# FIDO2AUTH_003.net
KiCad netlist of a schematic drawn in EAGLE
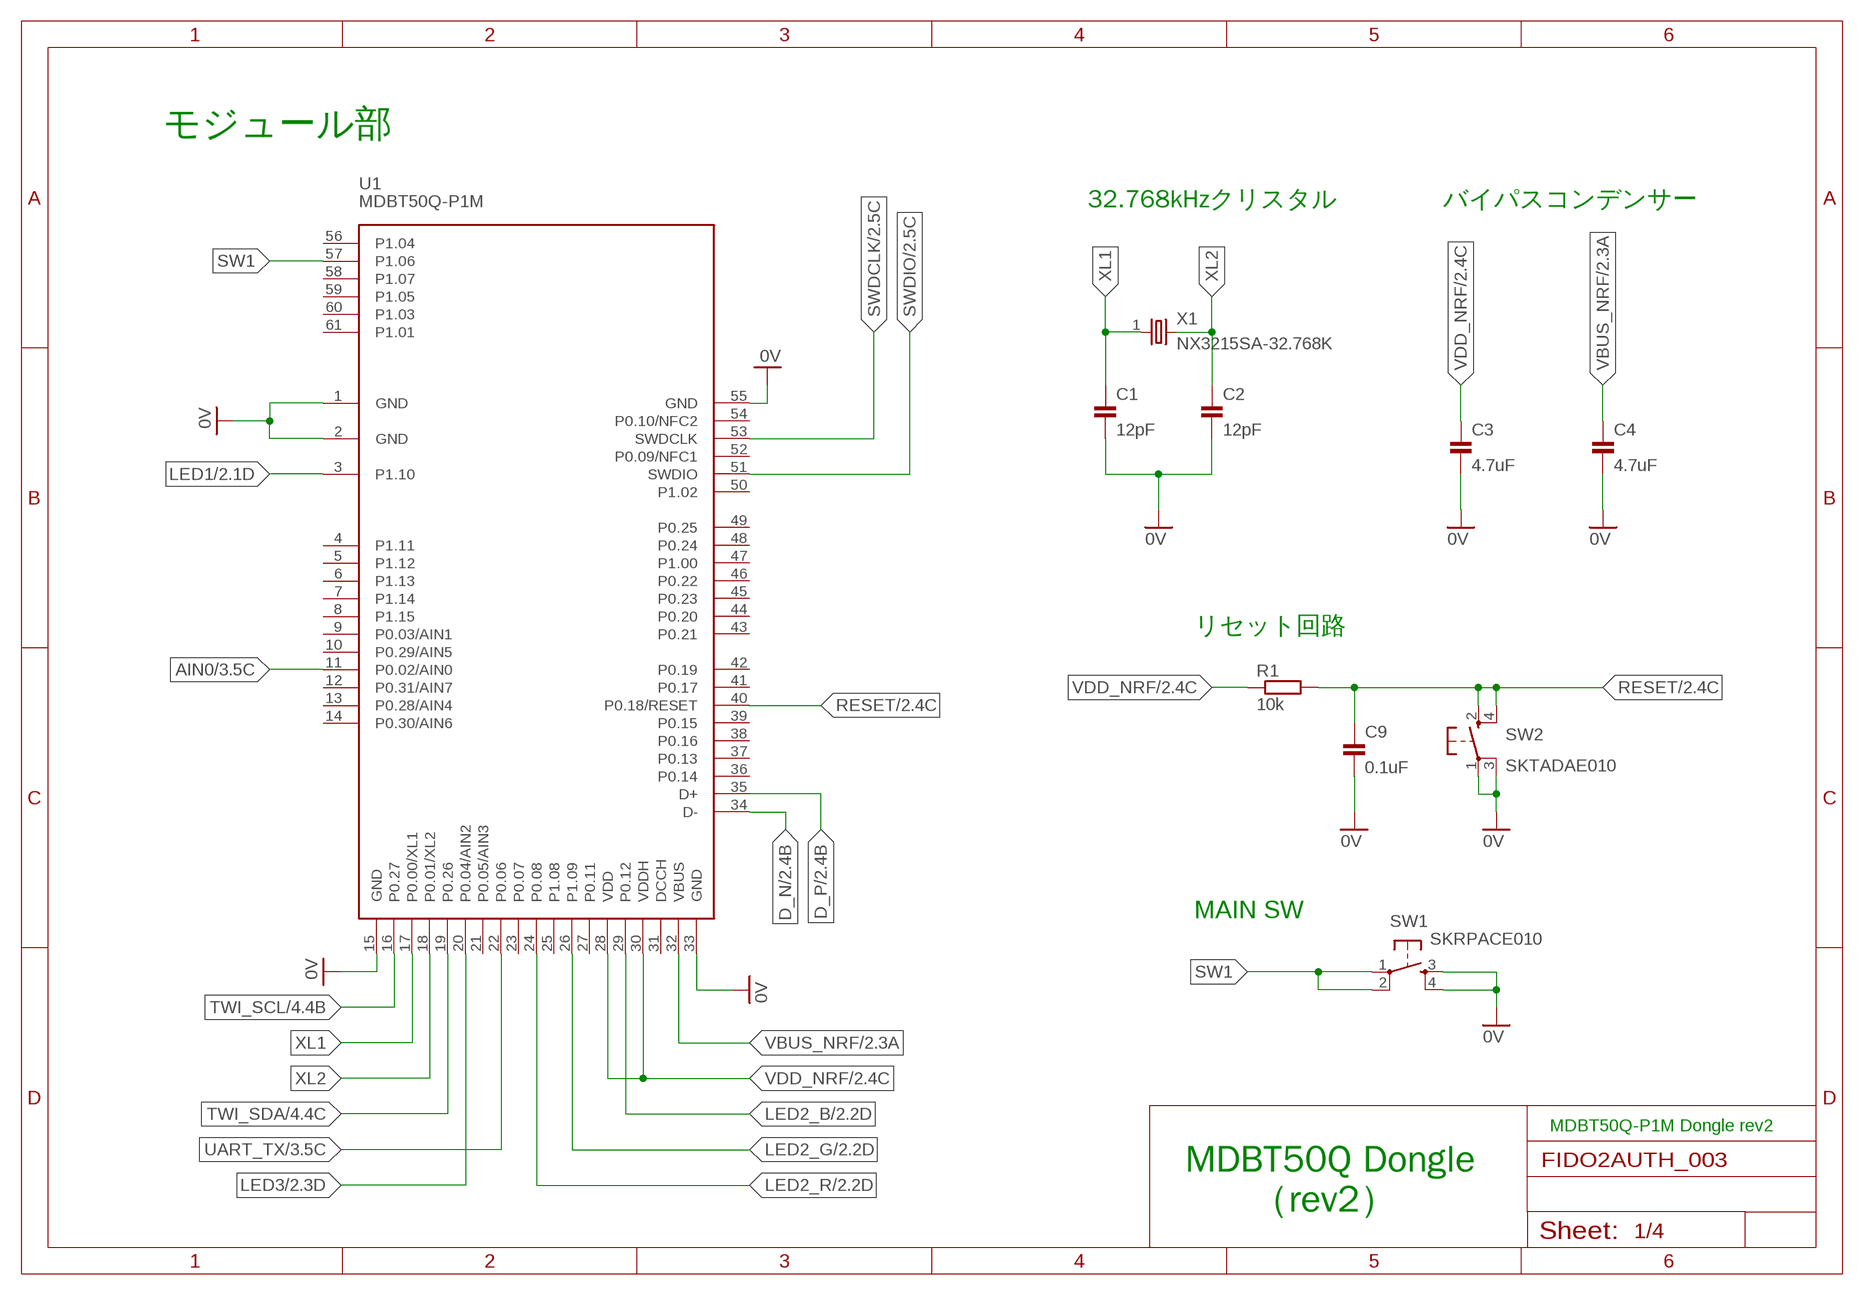
[diagram p0: schematic, sheet 1]
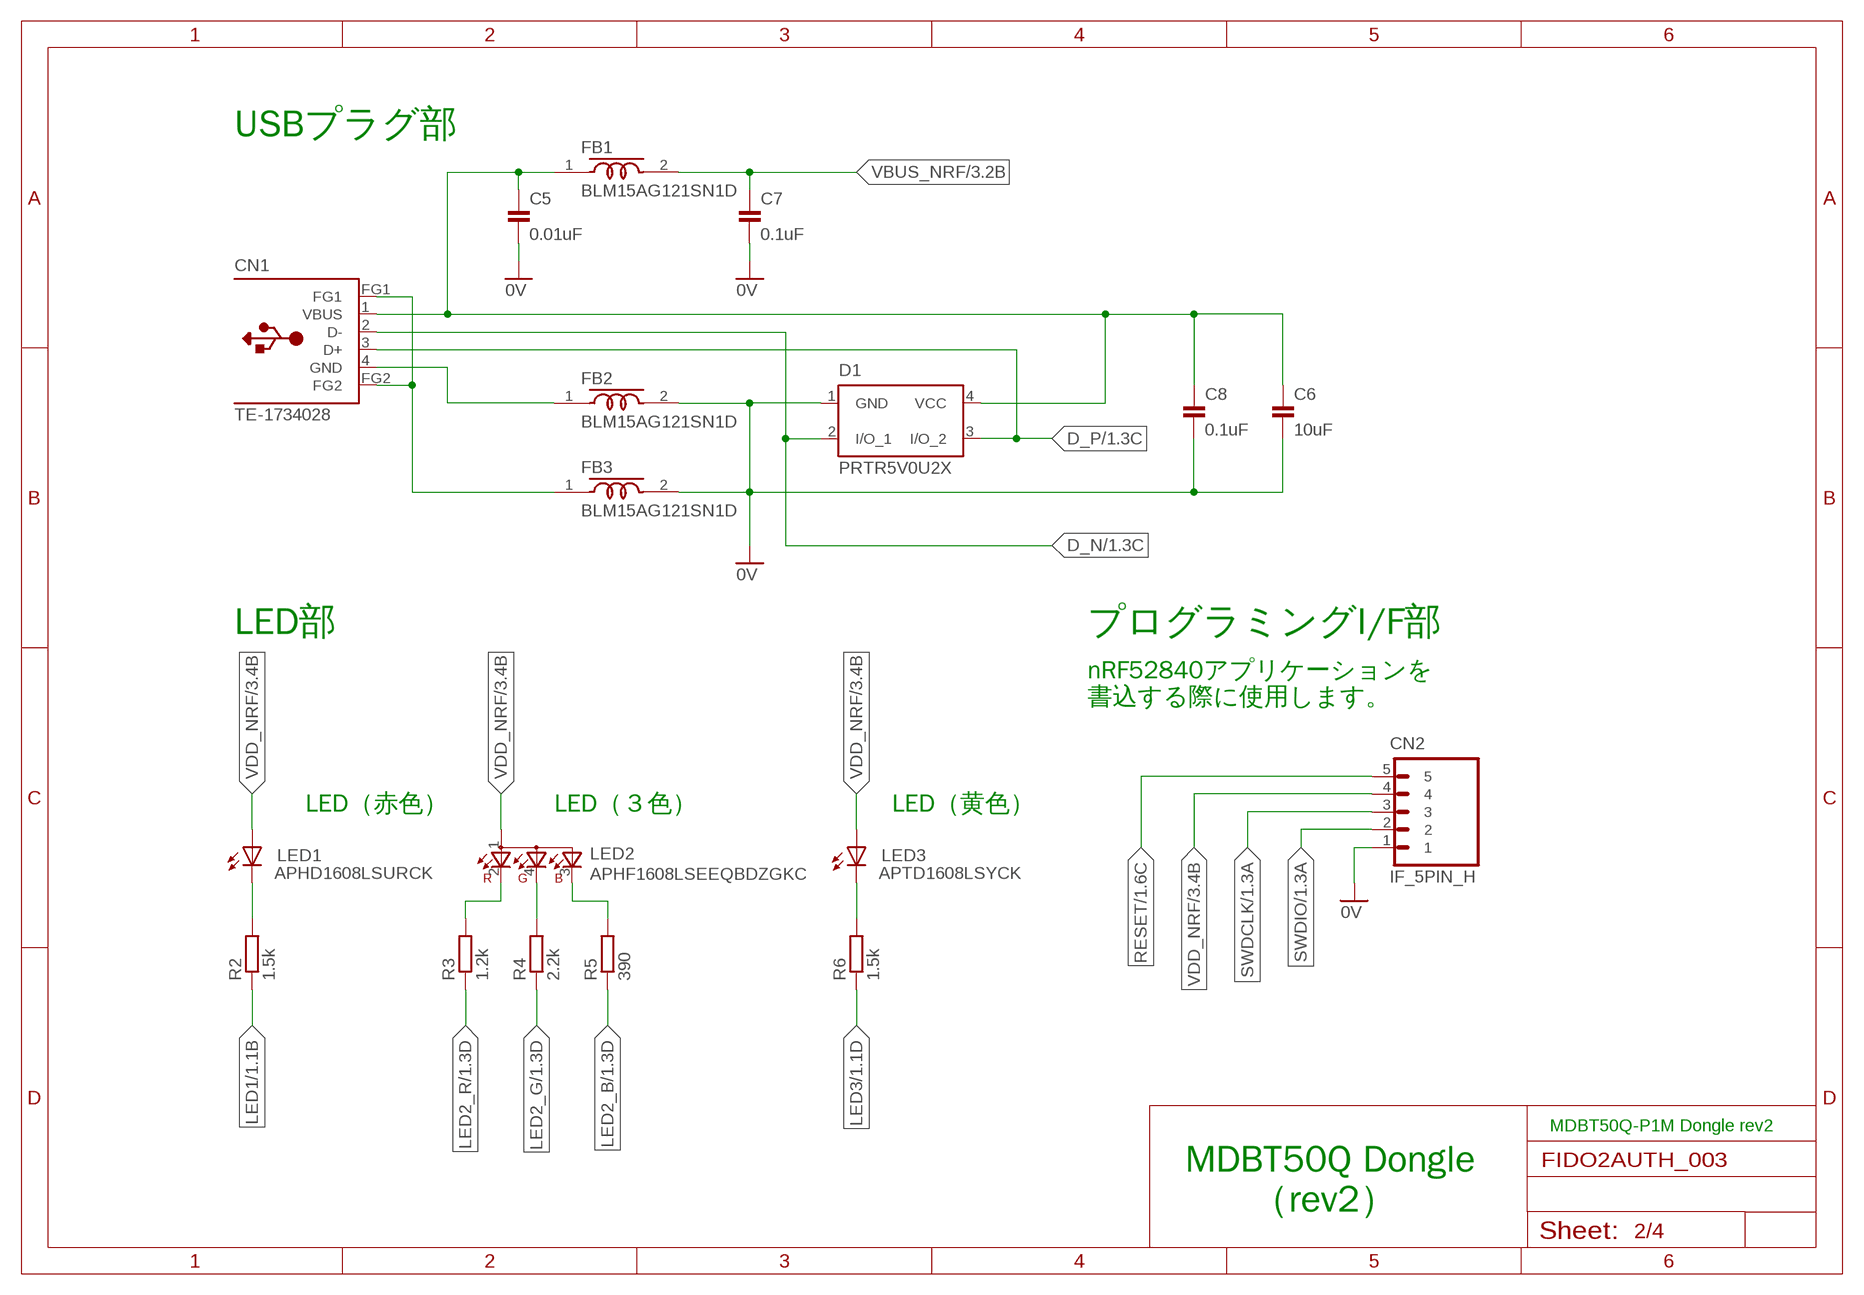
[diagram p1: schematic, sheet 2]
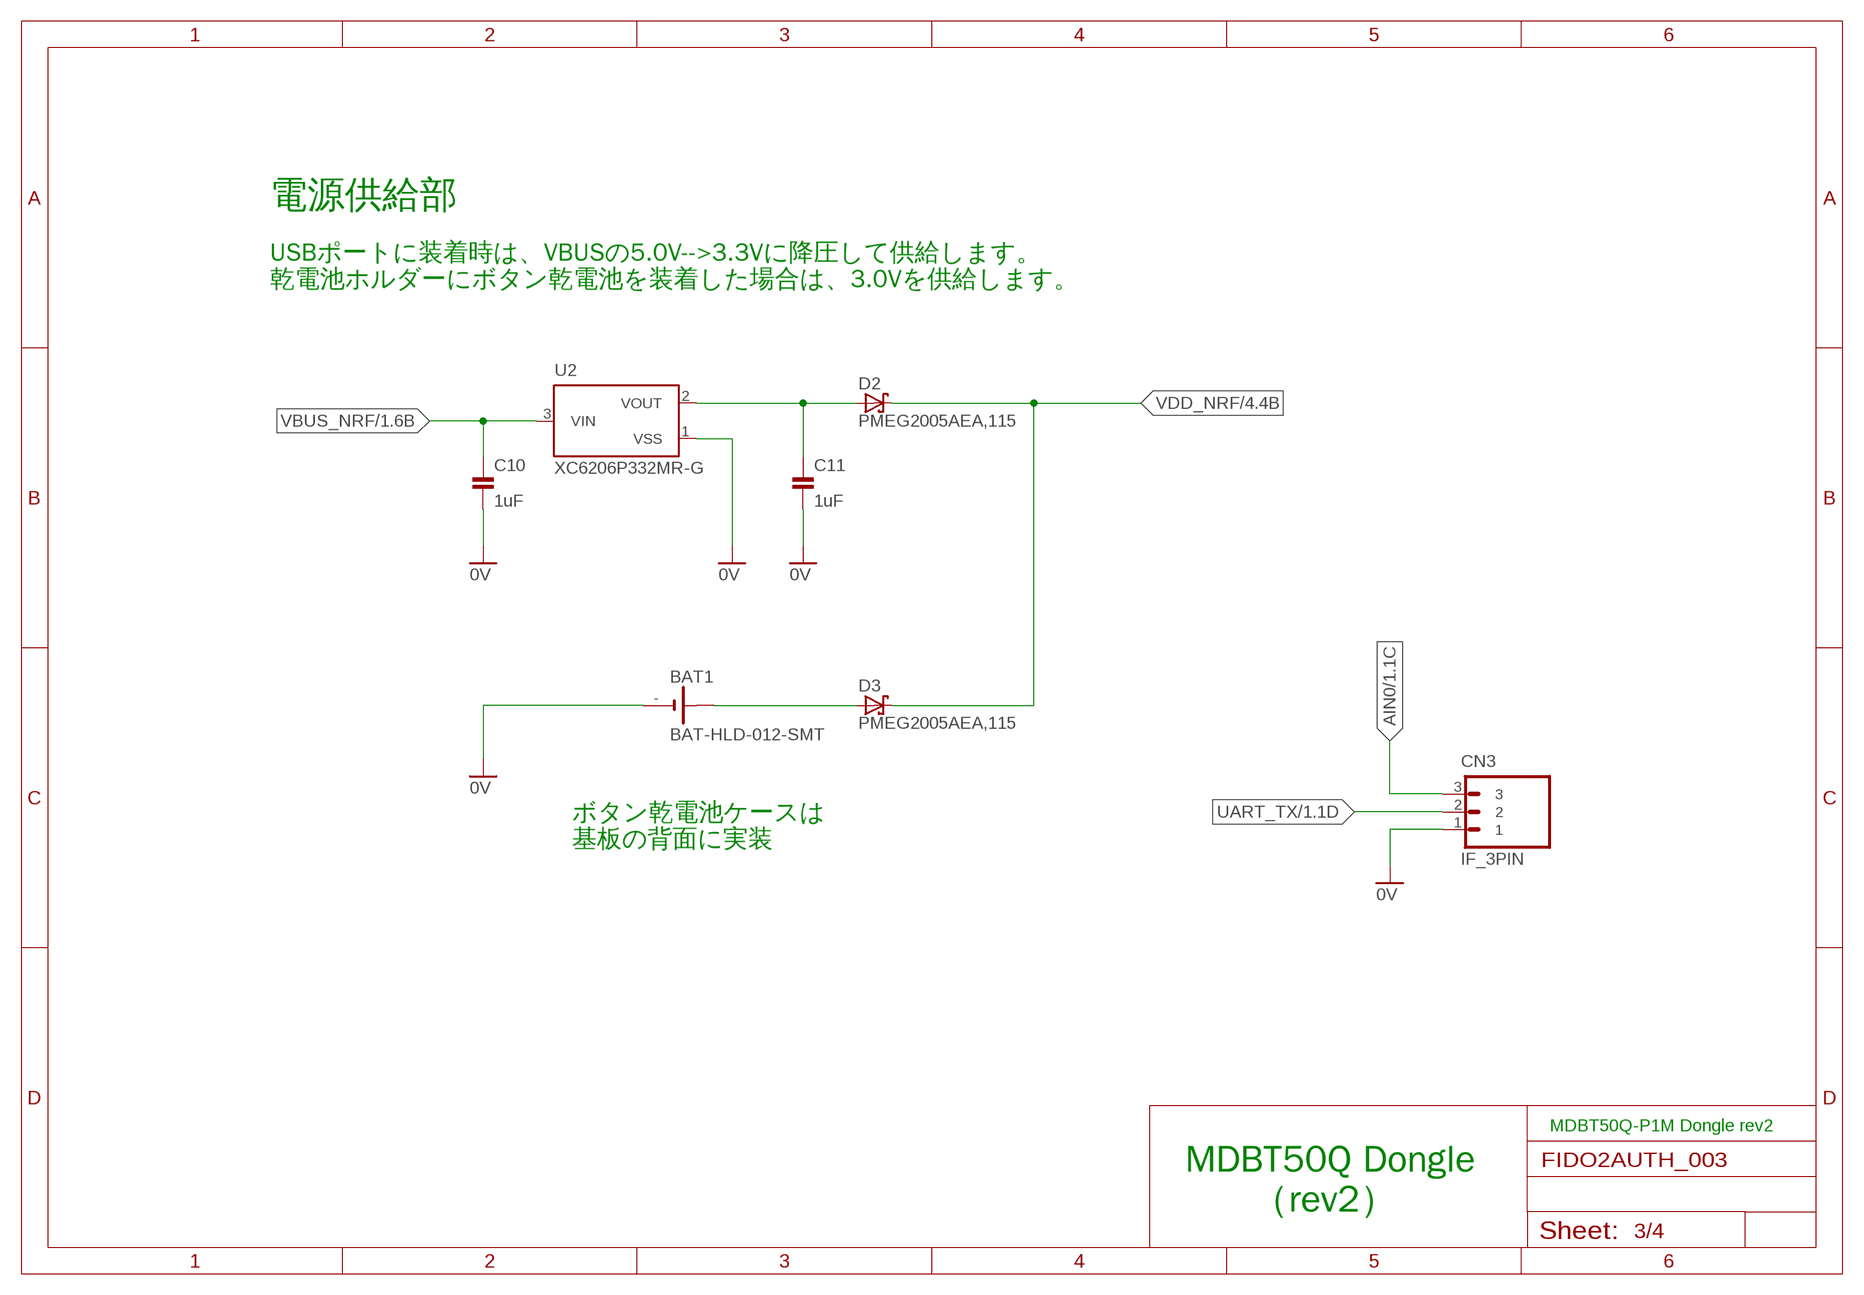
[diagram p2: schematic, sheet 3]
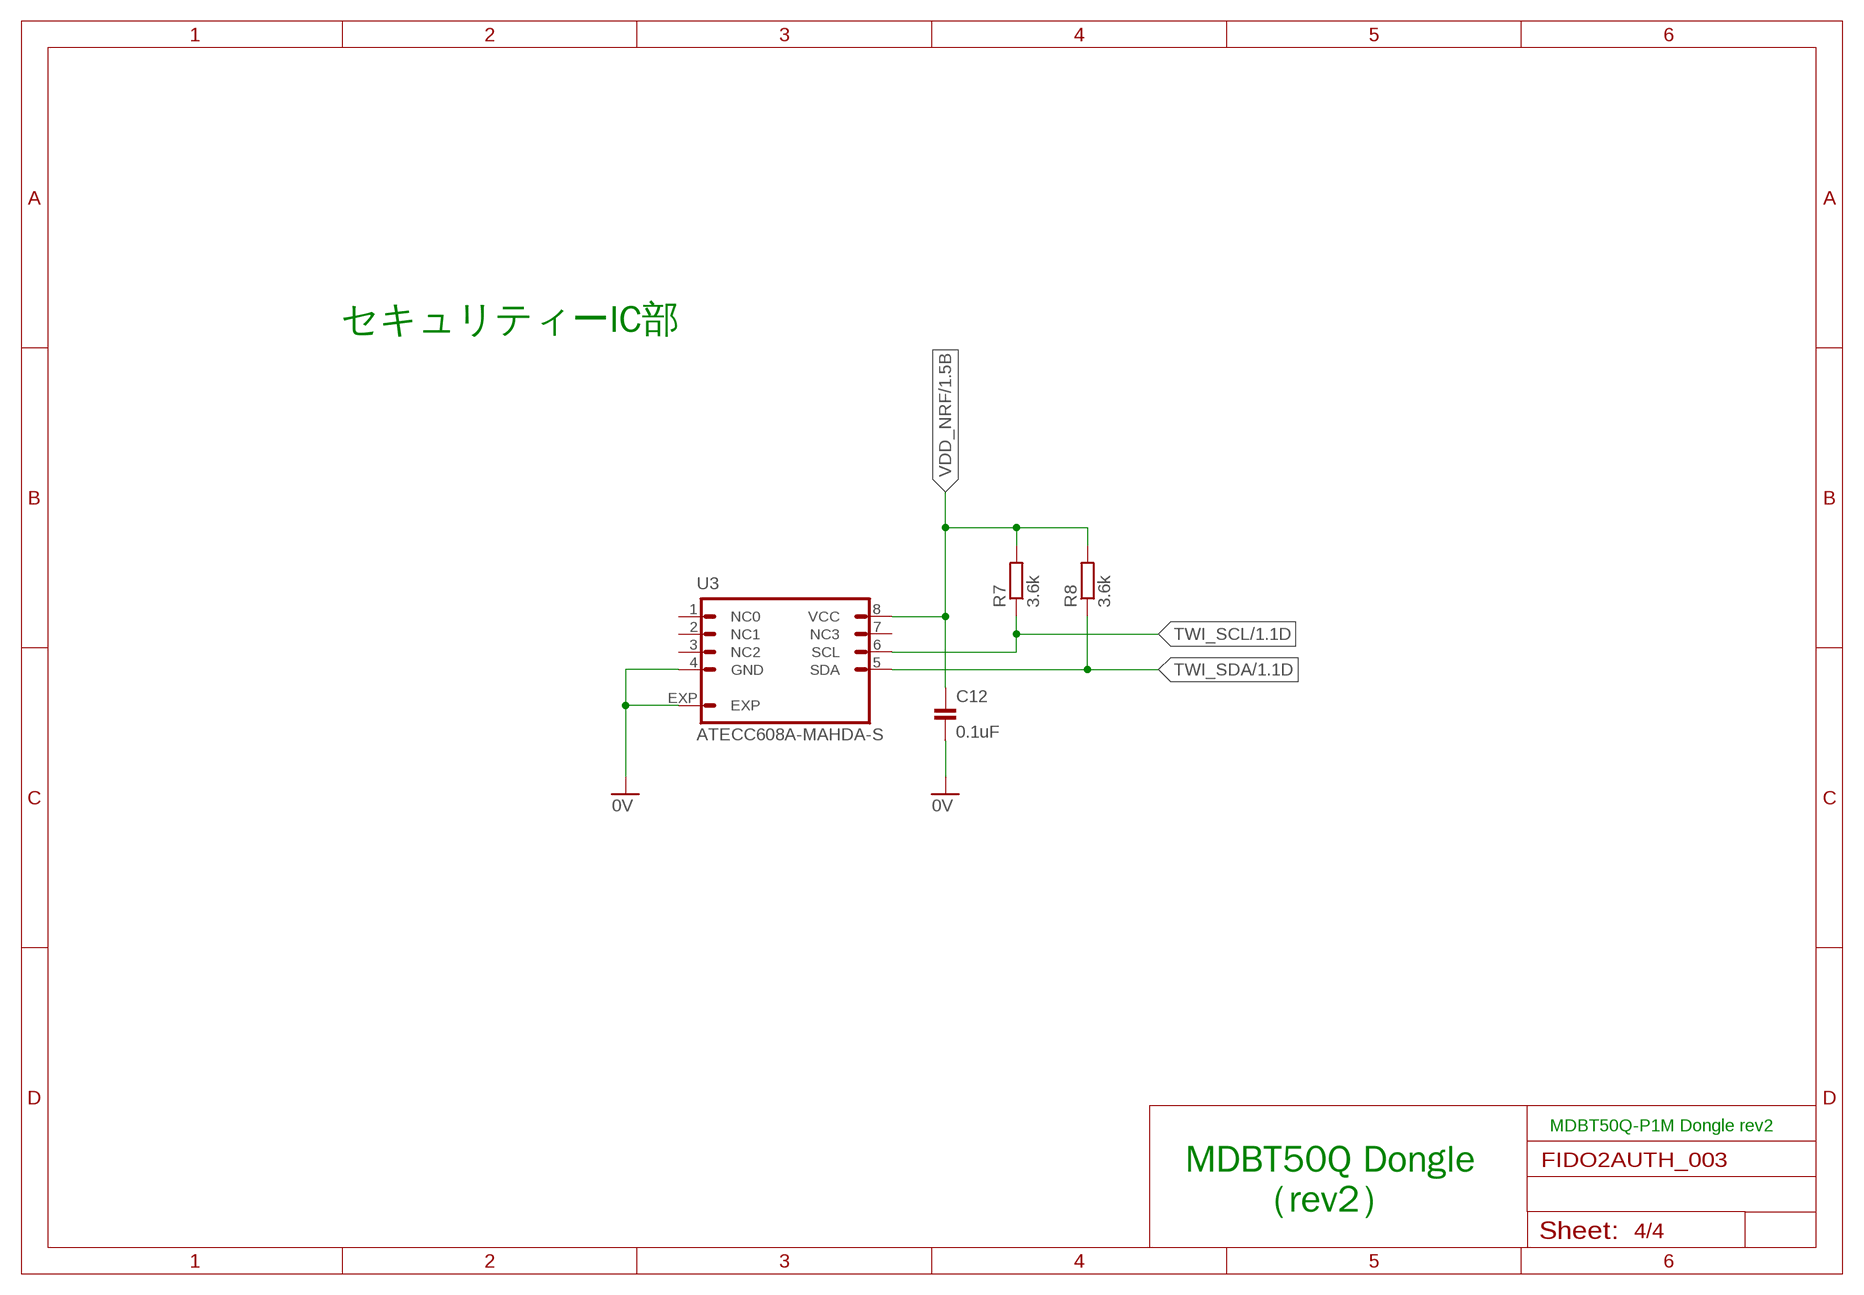
[diagram p3: schematic, sheet 4]

(export (version "E")
  (design (tool "Eeschema 10.0.6"))
  (components
    (comp (ref "C12")
      (value "0.1uF")
      (footprint "eagle-import:C0402K")
      (libsource (lib "eagle-import") (part "CAP_0402"))
    )
    (comp (ref "R7")
      (value "3.6k")
      (footprint "eagle-import:R0402")
      (libsource (lib "eagle-import") (part "RESISTOR_0402"))
    )
    (comp (ref "R8")
      (value "3.6k")
      (footprint "eagle-import:R0402")
      (libsource (lib "eagle-import") (part "RESISTOR_0402"))
    )
    (comp (ref "U3")
      (value "ATECC608A-MAHDA-S")
      (footprint "eagle-import:DFN-2X3")
      (libsource (lib "eagle-import") (part "ATECC608A-MAHDA-S"))
    )
    (comp (ref "C5")
      (value "0.01uF")
      (footprint "eagle-import:C0603K")
      (libsource (lib "eagle-import") (part "CAP_0603"))
    )
    (comp (ref "C6")
      (value "10uF")
      (footprint "eagle-import:C0603K")
      (libsource (lib "eagle-import") (part "CAP_0603"))
    )
    (comp (ref "C7")
      (value "0.1uF")
      (footprint "eagle-import:C0603K")
      (libsource (lib "eagle-import") (part "CAP_0603"))
    )
    (comp (ref "C8")
      (value "0.1uF")
      (footprint "eagle-import:C0603K")
      (libsource (lib "eagle-import") (part "CAP_0603"))
    )
    (comp (ref "CN1")
      (value "TE-1734028")
      (footprint "eagle-import:TE-1734028")
      (libsource (lib "eagle-import") (part "TE-1734028"))
    )
    (comp (ref "CN2")
      (value "IF_5PIN_H")
      (footprint "eagle-import:HEADER_5PIN")
      (libsource (lib "eagle-import") (part "IF_5PIN_H"))
    )
    (comp (ref "D1")
      (value "PRTR5V0U2X")
      (footprint "eagle-import:SOT143B")
      (libsource (lib "eagle-import") (part "PRTR5V0U2X"))
    )
    (comp (ref "FB1")
      (value "BLM15AG121SN1D")
      (footprint "eagle-import:C0402K@1")
      (libsource (lib "eagle-import") (part "BLM15AG121SN1D"))
    )
    (comp (ref "FB2")
      (value "BLM15AG121SN1D")
      (footprint "eagle-import:C0402K@1")
      (libsource (lib "eagle-import") (part "BLM15AG121SN1D"))
    )
    (comp (ref "FB3")
      (value "BLM15AG121SN1D")
      (footprint "eagle-import:C0402K@1")
      (libsource (lib "eagle-import") (part "BLM15AG121SN1D"))
    )
    (comp (ref "LED1")
      (value "APHD1608LSURCK")
      (footprint "eagle-import:CHIPLED_0603")
      (libsource (lib "eagle-import") (part "APHD1608LSURCK"))
    )
    (comp (ref "LED2")
      (value "APHF1608LSEEQBDZGKC")
      (footprint "eagle-import:APHF1608LSEEQBDZGKC")
      (libsource (lib "eagle-import") (part "APHF1608LSEEQBDZGKC"))
    )
    (comp (ref "LED3")
      (value "APTD1608LSYCK")
      (footprint "eagle-import:CHIPLED_0603")
      (libsource (lib "eagle-import") (part "APTD1608LSYCK"))
    )
    (comp (ref "R2")
      (value "1.5k")
      (footprint "eagle-import:R0603")
      (libsource (lib "eagle-import") (part "RESISTOR_0603"))
    )
    (comp (ref "R3")
      (value "1.2k")
      (footprint "eagle-import:R0603")
      (libsource (lib "eagle-import") (part "RESISTOR_0603"))
    )
    (comp (ref "R4")
      (value "2.2k")
      (footprint "eagle-import:R0603")
      (libsource (lib "eagle-import") (part "RESISTOR_0603"))
    )
    (comp (ref "R5")
      (value "390")
      (footprint "eagle-import:R0603")
      (libsource (lib "eagle-import") (part "RESISTOR_0603"))
    )
    (comp (ref "R6")
      (value "1.5k")
      (footprint "eagle-import:R0603")
      (libsource (lib "eagle-import") (part "RESISTOR_0603"))
    )
    (comp (ref "C1")
      (value "12pF")
      (footprint "eagle-import:C0603K")
      (libsource (lib "eagle-import") (part "CAP_0603"))
    )
    (comp (ref "C2")
      (value "12pF")
      (footprint "eagle-import:C0603K")
      (libsource (lib "eagle-import") (part "CAP_0603"))
    )
    (comp (ref "C3")
      (value "4.7uF")
      (footprint "eagle-import:C0603K")
      (libsource (lib "eagle-import") (part "CAP_0603"))
    )
    (comp (ref "C4")
      (value "4.7uF")
      (footprint "eagle-import:C0603K")
      (libsource (lib "eagle-import") (part "CAP_0603"))
    )
    (comp (ref "C9")
      (value "0.1uF")
      (footprint "eagle-import:C0603K")
      (libsource (lib "eagle-import") (part "CAP_0603"))
    )
    (comp (ref "R1")
      (value "10k")
      (footprint "eagle-import:R0603")
      (libsource (lib "eagle-import") (part "RESISTOR_0603"))
    )
    (comp (ref "SW1")
      (value "SKRPACE010")
      (footprint "eagle-import:SKRPACE010")
      (libsource (lib "eagle-import") (part "SKRPACE010"))
    )
    (comp (ref "SW2")
      (value "SKTADAE010")
      (footprint "eagle-import:SKTADAE010")
      (libsource (lib "eagle-import") (part "SKTADAE010"))
    )
    (comp (ref "U1")
      (value "MDBT50Q-P1M")
      (footprint "eagle-import:MDBT50Q-P1M")
      (libsource (lib "eagle-import") (part "MDBT50Q-P1M"))
    )
    (comp (ref "X1")
      (value "NX3215SA-32.768K")
      (footprint "eagle-import:NX3215")
      (libsource (lib "eagle-import") (part "NX3215SA-32.768K"))
    )
    (comp (ref "BAT1")
      (value "BAT-HLD-012-SMT")
      (footprint "eagle-import:BAT-HLD-012-SMT")
      (libsource (lib "eagle-import") (part "BAT-HLD-012-SMT"))
    )
    (comp (ref "C10")
      (value "1uF")
      (footprint "eagle-import:C0603K")
      (libsource (lib "eagle-import") (part "CAP_0603"))
    )
    (comp (ref "C11")
      (value "1uF")
      (footprint "eagle-import:C0603K")
      (libsource (lib "eagle-import") (part "CAP_0603"))
    )
    (comp (ref "CN3")
      (value "IF_3PIN")
      (footprint "eagle-import:HEADER_3PIN")
      (libsource (lib "eagle-import") (part "IF_3PIN"))
    )
    (comp (ref "D2")
      (value "PMEG2005AEA,115")
      (footprint "eagle-import:SOD323-W")
      (libsource (lib "eagle-import") (part "PMEG2005AEA,115"))
    )
    (comp (ref "D3")
      (value "PMEG2005AEA,115")
      (footprint "eagle-import:SOD323-W")
      (libsource (lib "eagle-import") (part "PMEG2005AEA,115"))
    )
    (comp (ref "U2")
      (value "XC6206P332MR-G")
      (footprint "eagle-import:SOT23")
      (libsource (lib "eagle-import") (part "XC6206P332MR-G"))
    )
  )
  (nets
    (net (code "1") (name "0V") (class "Default")
      (node (ref "BAT1") (pin "-") (pinfunction "-_-") (pintype "passive"))
      (node (ref "C1") (pin "2") (pinfunction "2_2") (pintype "passive"))
      (node (ref "C10") (pin "2") (pinfunction "2_2") (pintype "passive"))
      (node (ref "C11") (pin "2") (pinfunction "2_2") (pintype "passive"))
      (node (ref "C12") (pin "2") (pinfunction "2_2") (pintype "passive"))
      (node (ref "C2") (pin "2") (pinfunction "2_2") (pintype "passive"))
      (node (ref "C3") (pin "2") (pinfunction "2_2") (pintype "passive"))
      (node (ref "C4") (pin "2") (pinfunction "2_2") (pintype "passive"))
      (node (ref "C5") (pin "2") (pinfunction "2_2") (pintype "passive"))
      (node (ref "C6") (pin "2") (pinfunction "2_2") (pintype "passive"))
      (node (ref "C7") (pin "2") (pinfunction "2_2") (pintype "passive"))
      (node (ref "C8") (pin "2") (pinfunction "2_2") (pintype "passive"))
      (node (ref "C9") (pin "2") (pinfunction "2_2") (pintype "passive"))
      (node (ref "CN2") (pin "1") (pinfunction "1_1") (pintype "passive"))
      (node (ref "CN3") (pin "1") (pinfunction "1_1") (pintype "passive"))
      (node (ref "D1") (pin "1") (pinfunction "GND_1") (pintype "passive"))
      (node (ref "FB2") (pin "2") (pinfunction "2_2") (pintype "passive"))
      (node (ref "FB3") (pin "2") (pinfunction "2_2") (pintype "passive"))
      (node (ref "SW1") (pin "3") (pinfunction "S_3") (pintype "passive"))
      (node (ref "SW1") (pin "4") (pinfunction "S1_4") (pintype "passive"))
      (node (ref "SW2") (pin "1") (pinfunction "P_1") (pintype "passive"))
      (node (ref "SW2") (pin "3") (pinfunction "P1_3") (pintype "passive"))
      (node (ref "U1") (pin "1") (pinfunction "GND_1") (pintype "bidirectional"))
      (node (ref "U1") (pin "15") (pinfunction "GND_15") (pintype "bidirectional"))
      (node (ref "U1") (pin "2") (pinfunction "GND_2") (pintype "bidirectional"))
      (node (ref "U1") (pin "33") (pinfunction "GND_33") (pintype "bidirectional"))
      (node (ref "U1") (pin "55") (pinfunction "GND_55") (pintype "bidirectional"))
      (node (ref "U2") (pin "1") (pinfunction "VSS_1") (pintype "passive"))
      (node (ref "U3") (pin "4") (pinfunction "GND_4") (pintype "passive"))
      (node (ref "U3") (pin "EXP") (pinfunction "EXP_EXP") (pintype "passive"))
    )
    (net (code "2") (name "AIN0") (class "Default")
      (node (ref "CN3") (pin "3") (pinfunction "3_3") (pintype "passive"))
      (node (ref "U1") (pin "11") (pinfunction "P0.02/AIN0_11") (pintype "bidirectional"))
    )
    (net (code "3") (name "D_N") (class "Default")
      (node (ref "CN1") (pin "2") (pinfunction "D-_2") (pintype "bidirectional"))
      (node (ref "D1") (pin "2") (pinfunction "I/O_1_2") (pintype "bidirectional"))
      (node (ref "U1") (pin "34") (pinfunction "D-_34") (pintype "bidirectional"))
    )
    (net (code "4") (name "D_P") (class "Default")
      (node (ref "CN1") (pin "3") (pinfunction "D+_3") (pintype "bidirectional"))
      (node (ref "D1") (pin "3") (pinfunction "I/O_2_3") (pintype "bidirectional"))
      (node (ref "U1") (pin "35") (pinfunction "D+_35") (pintype "bidirectional"))
    )
    (net (code "5") (name "LED1") (class "Default")
      (node (ref "R2") (pin "1") (pinfunction "1_1") (pintype "passive"))
      (node (ref "U1") (pin "3") (pinfunction "P1.10_3") (pintype "bidirectional"))
    )
    (net (code "6") (name "LED2_B") (class "Default")
      (node (ref "R5") (pin "1") (pinfunction "1_1") (pintype "passive"))
      (node (ref "U1") (pin "29") (pinfunction "P0.12_29") (pintype "bidirectional"))
    )
    (net (code "7") (name "LED2_G") (class "Default")
      (node (ref "R4") (pin "1") (pinfunction "1_1") (pintype "passive"))
      (node (ref "U1") (pin "26") (pinfunction "P1.09_26") (pintype "bidirectional"))
    )
    (net (code "8") (name "LED2_R") (class "Default")
      (node (ref "R3") (pin "1") (pinfunction "1_1") (pintype "passive"))
      (node (ref "U1") (pin "24") (pinfunction "P0.08_24") (pintype "bidirectional"))
    )
    (net (code "9") (name "LED3") (class "Default")
      (node (ref "R6") (pin "1") (pinfunction "1_1") (pintype "passive"))
      (node (ref "U1") (pin "20") (pinfunction "P0.04/AIN2_20") (pintype "bidirectional"))
    )
    (net (code "10") (name "Net-(BAT1-+)") (class "Default")
      (node (ref "BAT1") (pin "+@1") (pinfunction "+_+@1") (pintype "passive"))
      (node (ref "D3") (pin "A") (pinfunction "A_A") (pintype "passive"))
    )
    (net (code "11") (name "Net-(CN1-GND)") (class "Default")
      (node (ref "CN1") (pin "4") (pinfunction "GND_4") (pintype "passive"))
      (node (ref "FB2") (pin "1") (pinfunction "1_1") (pintype "passive"))
    )
    (net (code "12") (name "Net-(CN1-PadFG1)") (class "Default")
      (node (ref "CN1") (pin "FG1") (pinfunction "FG1_FG1") (pintype "passive"))
      (node (ref "CN1") (pin "FG2") (pinfunction "FG2_FG2") (pintype "passive"))
      (node (ref "FB3") (pin "1") (pinfunction "1_1") (pintype "passive"))
    )
    (net (code "13") (name "Net-(CN1-VBUS)") (class "Default")
      (node (ref "C5") (pin "1") (pinfunction "1_1") (pintype "passive"))
      (node (ref "C6") (pin "1") (pinfunction "1_1") (pintype "passive"))
      (node (ref "C8") (pin "1") (pinfunction "1_1") (pintype "passive"))
      (node (ref "CN1") (pin "1") (pinfunction "VBUS_1") (pintype "passive"))
      (node (ref "D1") (pin "4") (pinfunction "VCC_4") (pintype "passive"))
      (node (ref "FB1") (pin "1") (pinfunction "1_1") (pintype "passive"))
    )
    (net (code "14") (name "Net-(LED1-PadC)") (class "Default")
      (node (ref "LED1") (pin "C") (pinfunction "C_C") (pintype "passive"))
      (node (ref "R2") (pin "2") (pinfunction "2_2") (pintype "passive"))
    )
    (net (code "15") (name "Net-(LED2-CBLUE)") (class "Default")
      (node (ref "LED2") (pin "3") (pinfunction "CBLUE_3") (pintype "passive"))
      (node (ref "R5") (pin "2") (pinfunction "2_2") (pintype "passive"))
    )
    (net (code "16") (name "Net-(LED2-CGREEN)") (class "Default")
      (node (ref "LED2") (pin "4") (pinfunction "CGREEN_4") (pintype "passive"))
      (node (ref "R4") (pin "2") (pinfunction "2_2") (pintype "passive"))
    )
    (net (code "17") (name "Net-(LED2-CRED)") (class "Default")
      (node (ref "LED2") (pin "2") (pinfunction "CRED_2") (pintype "passive"))
      (node (ref "R3") (pin "2") (pinfunction "2_2") (pintype "passive"))
    )
    (net (code "18") (name "Net-(LED3-PadC)") (class "Default")
      (node (ref "LED3") (pin "C") (pinfunction "C_C") (pintype "passive"))
      (node (ref "R6") (pin "2") (pinfunction "2_2") (pintype "passive"))
    )
    (net (code "19") (name "Net-(U2-VOUT)") (class "Default")
      (node (ref "C11") (pin "1") (pinfunction "1_1") (pintype "passive"))
      (node (ref "D2") (pin "A") (pinfunction "A_A") (pintype "passive"))
      (node (ref "U2") (pin "2") (pinfunction "VOUT_2") (pintype "passive"))
    )
    (net (code "20") (name "RESET") (class "Default")
      (node (ref "C9") (pin "1") (pinfunction "1_1") (pintype "passive"))
      (node (ref "CN2") (pin "5") (pinfunction "5_5") (pintype "passive"))
      (node (ref "R1") (pin "2") (pinfunction "2_2") (pintype "passive"))
      (node (ref "SW2") (pin "2") (pinfunction "S_2") (pintype "passive"))
      (node (ref "SW2") (pin "4") (pinfunction "S1_4") (pintype "passive"))
      (node (ref "U1") (pin "40") (pinfunction "P0.18/RESET_40") (pintype "bidirectional"))
    )
    (net (code "21") (name "SW1") (class "Default")
      (node (ref "SW1") (pin "1") (pinfunction "P_1") (pintype "passive"))
      (node (ref "SW1") (pin "2") (pinfunction "P1_2") (pintype "passive"))
      (node (ref "U1") (pin "57") (pinfunction "P1.06_57") (pintype "bidirectional"))
    )
    (net (code "22") (name "SWDCLK") (class "Default")
      (node (ref "CN2") (pin "3") (pinfunction "3_3") (pintype "passive"))
      (node (ref "U1") (pin "53") (pinfunction "SWDCLK_53") (pintype "bidirectional"))
    )
    (net (code "23") (name "SWDIO") (class "Default")
      (node (ref "CN2") (pin "2") (pinfunction "2_2") (pintype "passive"))
      (node (ref "U1") (pin "51") (pinfunction "SWDIO_51") (pintype "bidirectional"))
    )
    (net (code "24") (name "TWI_SCL") (class "Default")
      (node (ref "R7") (pin "1") (pinfunction "1_1") (pintype "passive"))
      (node (ref "U1") (pin "16") (pinfunction "P0.27_16") (pintype "bidirectional"))
      (node (ref "U3") (pin "6") (pinfunction "SCL_6") (pintype "bidirectional"))
    )
    (net (code "25") (name "TWI_SDA") (class "Default")
      (node (ref "R8") (pin "1") (pinfunction "1_1") (pintype "passive"))
      (node (ref "U1") (pin "19") (pinfunction "P0.26_19") (pintype "bidirectional"))
      (node (ref "U3") (pin "5") (pinfunction "SDA_5") (pintype "bidirectional"))
    )
    (net (code "26") (name "UART_TX") (class "Default")
      (node (ref "CN3") (pin "2") (pinfunction "2_2") (pintype "passive"))
      (node (ref "U1") (pin "22") (pinfunction "P0.06_22") (pintype "bidirectional"))
    )
    (net (code "27") (name "VBUS_NRF") (class "Default")
      (node (ref "C10") (pin "1") (pinfunction "1_1") (pintype "passive"))
      (node (ref "C4") (pin "1") (pinfunction "1_1") (pintype "passive"))
      (node (ref "C7") (pin "1") (pinfunction "1_1") (pintype "passive"))
      (node (ref "FB1") (pin "2") (pinfunction "2_2") (pintype "passive"))
      (node (ref "U1") (pin "32") (pinfunction "VBUS_32") (pintype "bidirectional"))
      (node (ref "U2") (pin "3") (pinfunction "VIN_3") (pintype "passive"))
    )
    (net (code "28") (name "VDD_NRF") (class "Default")
      (node (ref "C12") (pin "1") (pinfunction "1_1") (pintype "passive"))
      (node (ref "C3") (pin "1") (pinfunction "1_1") (pintype "passive"))
      (node (ref "CN2") (pin "4") (pinfunction "4_4") (pintype "passive"))
      (node (ref "D2") (pin "C") (pinfunction "C_C") (pintype "passive"))
      (node (ref "D3") (pin "C") (pinfunction "C_C") (pintype "passive"))
      (node (ref "LED1") (pin "A") (pinfunction "A_A") (pintype "passive"))
      (node (ref "LED2") (pin "1") (pinfunction "A_1") (pintype "passive"))
      (node (ref "LED3") (pin "A") (pinfunction "A_A") (pintype "passive"))
      (node (ref "R1") (pin "1") (pinfunction "1_1") (pintype "passive"))
      (node (ref "R7") (pin "2") (pinfunction "2_2") (pintype "passive"))
      (node (ref "R8") (pin "2") (pinfunction "2_2") (pintype "passive"))
      (node (ref "U1") (pin "28") (pinfunction "VDD_28") (pintype "bidirectional"))
      (node (ref "U1") (pin "30") (pinfunction "VDDH_30") (pintype "bidirectional"))
      (node (ref "U3") (pin "8") (pinfunction "VCC_8") (pintype "passive"))
    )
    (net (code "29") (name "XL1") (class "Default")
      (node (ref "C1") (pin "1") (pinfunction "1_1") (pintype "passive"))
      (node (ref "U1") (pin "17") (pinfunction "P0.00/XL1_17") (pintype "bidirectional"))
      (node (ref "X1") (pin "1") (pinfunction "1_1") (pintype "passive"))
    )
    (net (code "30") (name "XL2") (class "Default")
      (node (ref "C2") (pin "1") (pinfunction "1_1") (pintype "passive"))
      (node (ref "U1") (pin "18") (pinfunction "P0.01/XL2_18") (pintype "bidirectional"))
      (node (ref "X1") (pin "2") (pinfunction "2_2") (pintype "passive"))
    )
    (net (code "31") (name "unconnected-(U1-DCCH-Pad31)") (class "Default")
      (node (ref "U1") (pin "31") (pinfunction "DCCH_31") (pintype "bidirectional"))
    )
    (net (code "32") (name "unconnected-(U1-P0.03{slash}AIN1-Pad9)") (class "Default")
      (node (ref "U1") (pin "9") (pinfunction "P0.03/AIN1_9") (pintype "bidirectional"))
    )
    (net (code "33") (name "unconnected-(U1-P0.05{slash}AIN3-Pad21)") (class "Default")
      (node (ref "U1") (pin "21") (pinfunction "P0.05/AIN3_21") (pintype "bidirectional"))
    )
    (net (code "34") (name "unconnected-(U1-P0.07-Pad23)") (class "Default")
      (node (ref "U1") (pin "23") (pinfunction "P0.07_23") (pintype "bidirectional"))
    )
    (net (code "35") (name "unconnected-(U1-P0.09{slash}NFC1-Pad52)") (class "Default")
      (node (ref "U1") (pin "52") (pinfunction "P0.09/NFC1_52") (pintype "bidirectional"))
    )
    (net (code "36") (name "unconnected-(U1-P0.10{slash}NFC2-Pad54)") (class "Default")
      (node (ref "U1") (pin "54") (pinfunction "P0.10/NFC2_54") (pintype "bidirectional"))
    )
    (net (code "37") (name "unconnected-(U1-P0.11-Pad27)") (class "Default")
      (node (ref "U1") (pin "27") (pinfunction "P0.11_27") (pintype "bidirectional"))
    )
    (net (code "38") (name "unconnected-(U1-P0.13-Pad37)") (class "Default")
      (node (ref "U1") (pin "37") (pinfunction "P0.13_37") (pintype "bidirectional"))
    )
    (net (code "39") (name "unconnected-(U1-P0.14-Pad36)") (class "Default")
      (node (ref "U1") (pin "36") (pinfunction "P0.14_36") (pintype "bidirectional"))
    )
    (net (code "40") (name "unconnected-(U1-P0.15-Pad39)") (class "Default")
      (node (ref "U1") (pin "39") (pinfunction "P0.15_39") (pintype "bidirectional"))
    )
    (net (code "41") (name "unconnected-(U1-P0.16-Pad38)") (class "Default")
      (node (ref "U1") (pin "38") (pinfunction "P0.16_38") (pintype "bidirectional"))
    )
    (net (code "42") (name "unconnected-(U1-P0.17-Pad41)") (class "Default")
      (node (ref "U1") (pin "41") (pinfunction "P0.17_41") (pintype "bidirectional"))
    )
    (net (code "43") (name "unconnected-(U1-P0.19-Pad42)") (class "Default")
      (node (ref "U1") (pin "42") (pinfunction "P0.19_42") (pintype "bidirectional"))
    )
    (net (code "44") (name "unconnected-(U1-P0.20-Pad44)") (class "Default")
      (node (ref "U1") (pin "44") (pinfunction "P0.20_44") (pintype "bidirectional"))
    )
    (net (code "45") (name "unconnected-(U1-P0.21-Pad43)") (class "Default")
      (node (ref "U1") (pin "43") (pinfunction "P0.21_43") (pintype "bidirectional"))
    )
    (net (code "46") (name "unconnected-(U1-P0.22-Pad46)") (class "Default")
      (node (ref "U1") (pin "46") (pinfunction "P0.22_46") (pintype "bidirectional"))
    )
    (net (code "47") (name "unconnected-(U1-P0.23-Pad45)") (class "Default")
      (node (ref "U1") (pin "45") (pinfunction "P0.23_45") (pintype "bidirectional"))
    )
    (net (code "48") (name "unconnected-(U1-P0.24-Pad48)") (class "Default")
      (node (ref "U1") (pin "48") (pinfunction "P0.24_48") (pintype "bidirectional"))
    )
    (net (code "49") (name "unconnected-(U1-P0.25-Pad49)") (class "Default")
      (node (ref "U1") (pin "49") (pinfunction "P0.25_49") (pintype "bidirectional"))
    )
    (net (code "50") (name "unconnected-(U1-P0.28{slash}AIN4-Pad13)") (class "Default")
      (node (ref "U1") (pin "13") (pinfunction "P0.28/AIN4_13") (pintype "bidirectional"))
    )
    (net (code "51") (name "unconnected-(U1-P0.29{slash}AIN5-Pad10)") (class "Default")
      (node (ref "U1") (pin "10") (pinfunction "P0.29/AIN5_10") (pintype "bidirectional"))
    )
    (net (code "52") (name "unconnected-(U1-P0.30{slash}AIN6-Pad14)") (class "Default")
      (node (ref "U1") (pin "14") (pinfunction "P0.30/AIN6_14") (pintype "bidirectional"))
    )
    (net (code "53") (name "unconnected-(U1-P0.31{slash}AIN7-Pad12)") (class "Default")
      (node (ref "U1") (pin "12") (pinfunction "P0.31/AIN7_12") (pintype "bidirectional"))
    )
    (net (code "54") (name "unconnected-(U1-P1.00-Pad47)") (class "Default")
      (node (ref "U1") (pin "47") (pinfunction "P1.00_47") (pintype "bidirectional"))
    )
    (net (code "55") (name "unconnected-(U1-P1.01-Pad61)") (class "Default")
      (node (ref "U1") (pin "61") (pinfunction "P1.01_61") (pintype "bidirectional"))
    )
    (net (code "56") (name "unconnected-(U1-P1.02-Pad50)") (class "Default")
      (node (ref "U1") (pin "50") (pinfunction "P1.02_50") (pintype "bidirectional"))
    )
    (net (code "57") (name "unconnected-(U1-P1.03-Pad60)") (class "Default")
      (node (ref "U1") (pin "60") (pinfunction "P1.03_60") (pintype "bidirectional"))
    )
    (net (code "58") (name "unconnected-(U1-P1.04-Pad56)") (class "Default")
      (node (ref "U1") (pin "56") (pinfunction "P1.04_56") (pintype "bidirectional"))
    )
    (net (code "59") (name "unconnected-(U1-P1.05-Pad59)") (class "Default")
      (node (ref "U1") (pin "59") (pinfunction "P1.05_59") (pintype "bidirectional"))
    )
    (net (code "60") (name "unconnected-(U1-P1.07-Pad58)") (class "Default")
      (node (ref "U1") (pin "58") (pinfunction "P1.07_58") (pintype "bidirectional"))
    )
    (net (code "61") (name "unconnected-(U1-P1.08-Pad25)") (class "Default")
      (node (ref "U1") (pin "25") (pinfunction "P1.08_25") (pintype "bidirectional"))
    )
    (net (code "62") (name "unconnected-(U1-P1.11-Pad4)") (class "Default")
      (node (ref "U1") (pin "4") (pinfunction "P1.11_4") (pintype "bidirectional"))
    )
    (net (code "63") (name "unconnected-(U1-P1.12-Pad5)") (class "Default")
      (node (ref "U1") (pin "5") (pinfunction "P1.12_5") (pintype "bidirectional"))
    )
    (net (code "64") (name "unconnected-(U1-P1.13-Pad6)") (class "Default")
      (node (ref "U1") (pin "6") (pinfunction "P1.13_6") (pintype "bidirectional"))
    )
    (net (code "65") (name "unconnected-(U1-P1.14-Pad7)") (class "Default")
      (node (ref "U1") (pin "7") (pinfunction "P1.14_7") (pintype "bidirectional"))
    )
    (net (code "66") (name "unconnected-(U1-P1.15-Pad8)") (class "Default")
      (node (ref "U1") (pin "8") (pinfunction "P1.15_8") (pintype "bidirectional"))
    )
    (net (code "67") (name "unconnected-(U3-NC0-Pad1)") (class "Default")
      (node (ref "U3") (pin "1") (pinfunction "NC0_1") (pintype "passive"))
    )
    (net (code "68") (name "unconnected-(U3-NC1-Pad2)") (class "Default")
      (node (ref "U3") (pin "2") (pinfunction "NC1_2") (pintype "passive"))
    )
    (net (code "69") (name "unconnected-(U3-NC2-Pad3)") (class "Default")
      (node (ref "U3") (pin "3") (pinfunction "NC2_3") (pintype "passive"))
    )
    (net (code "70") (name "unconnected-(U3-NC3-Pad7)") (class "Default")
      (node (ref "U3") (pin "7") (pinfunction "NC3_7") (pintype "passive"))
    )
  )
)
